# Netzteil_CA1.net
KiCad netlist of a schematic drawn in EAGLE
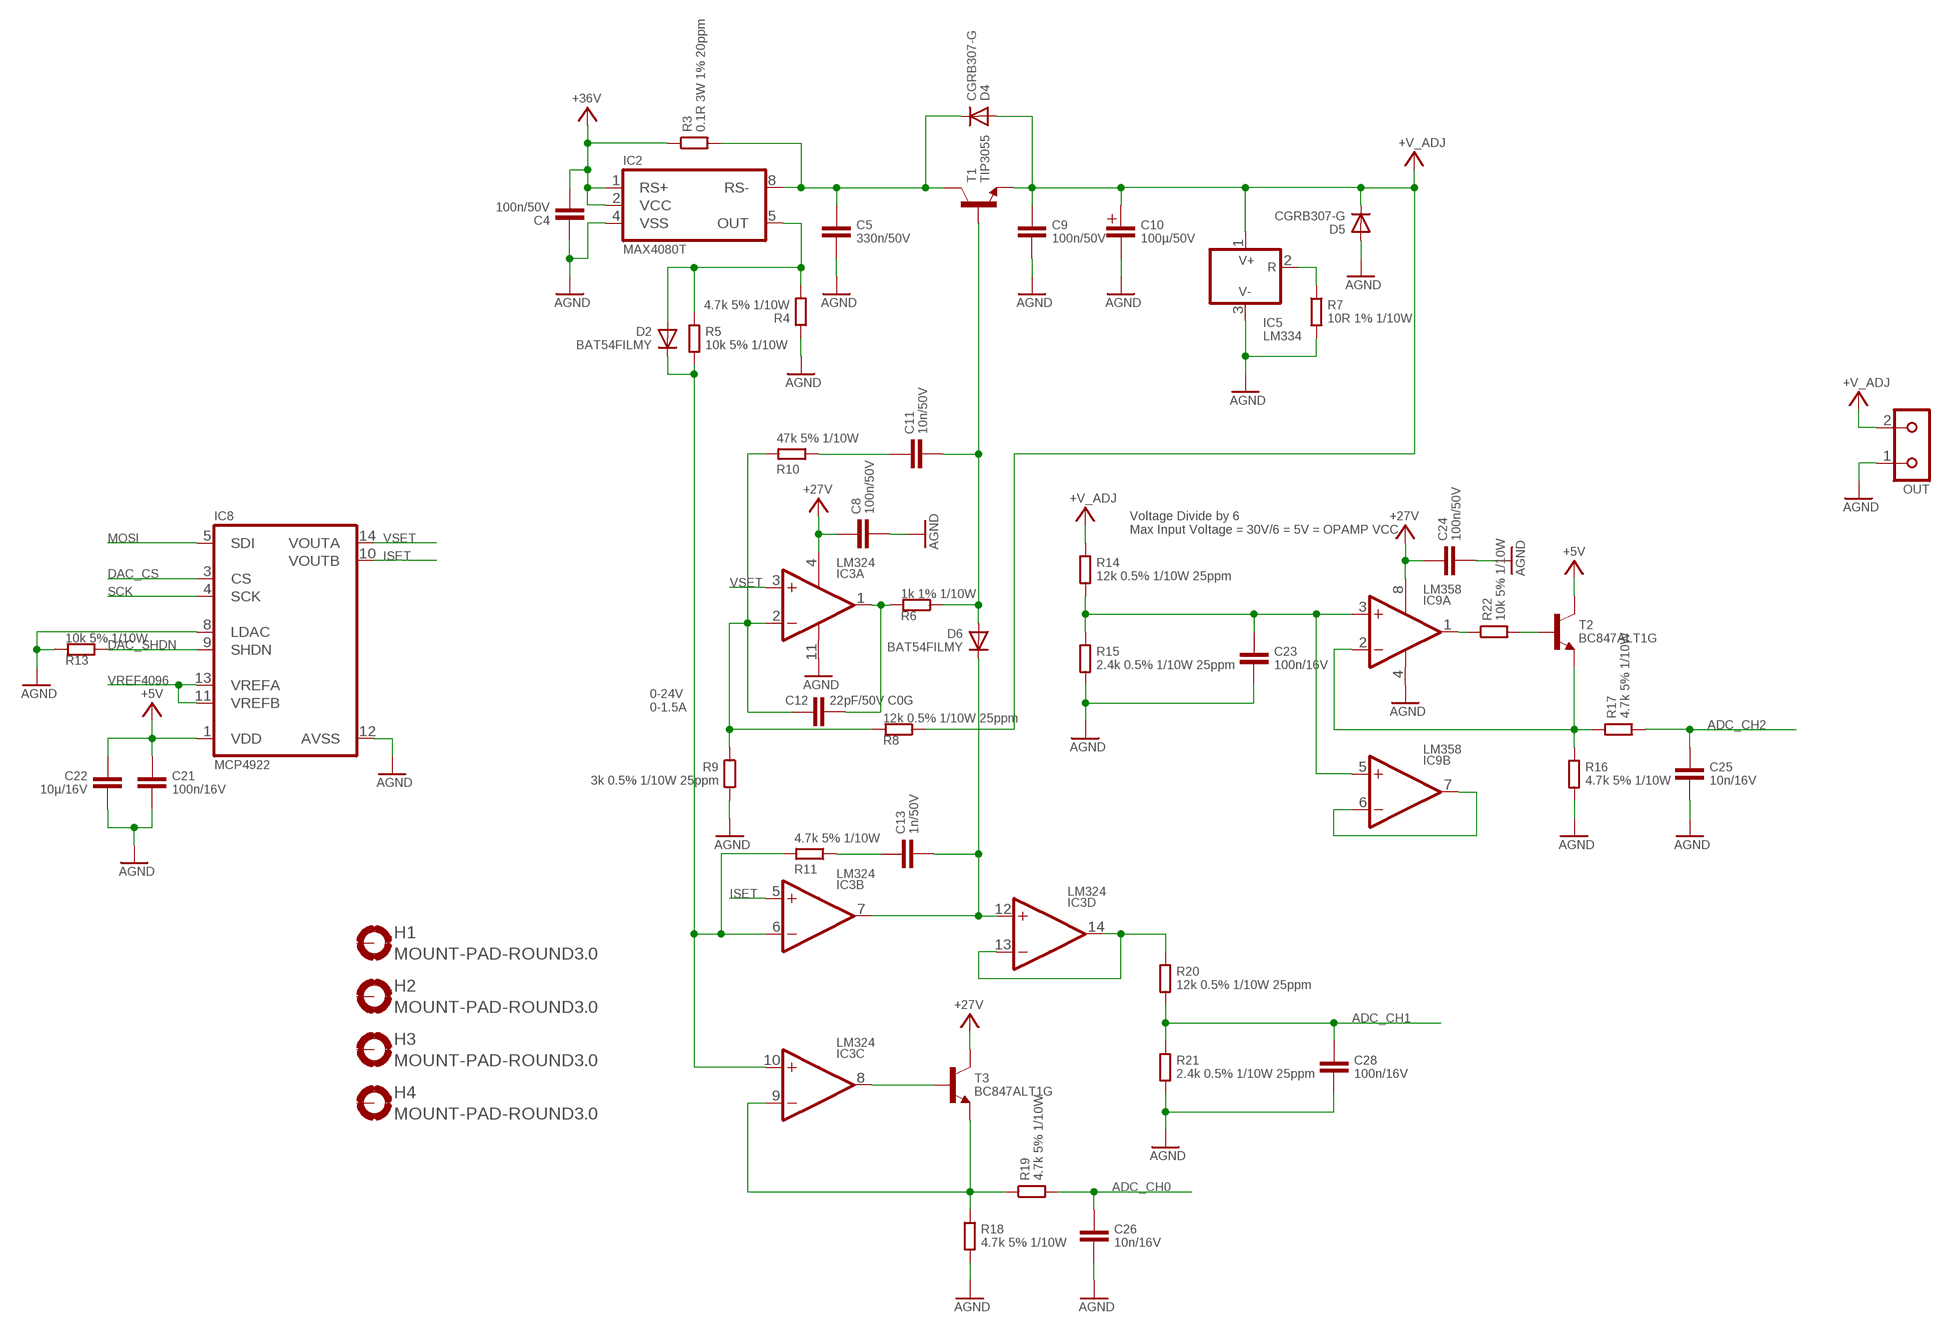
[diagram p0: schematic, sheet 1]
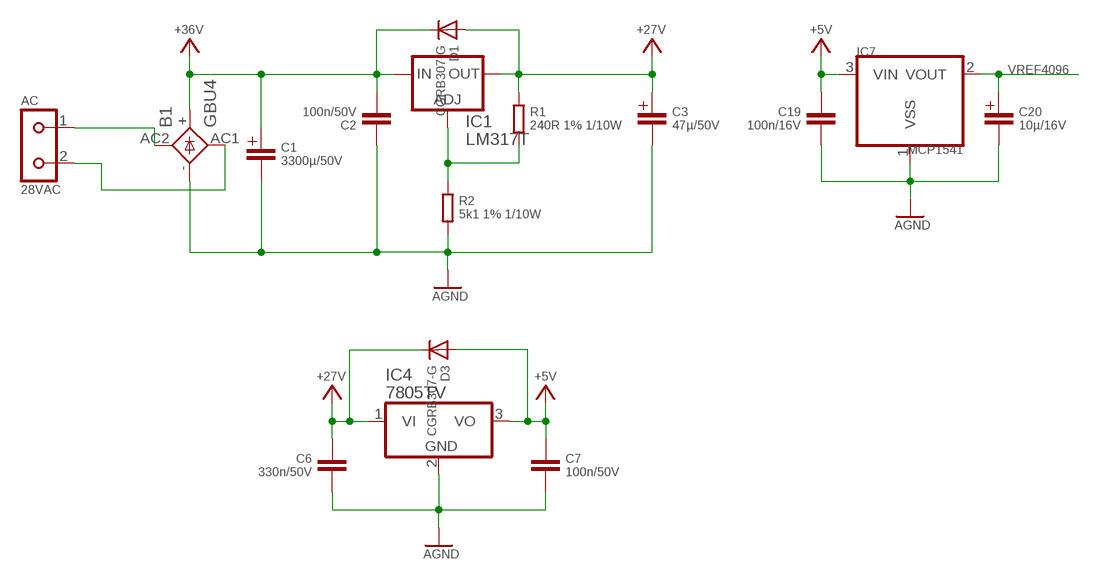
[diagram p1: schematic, sheet 2]
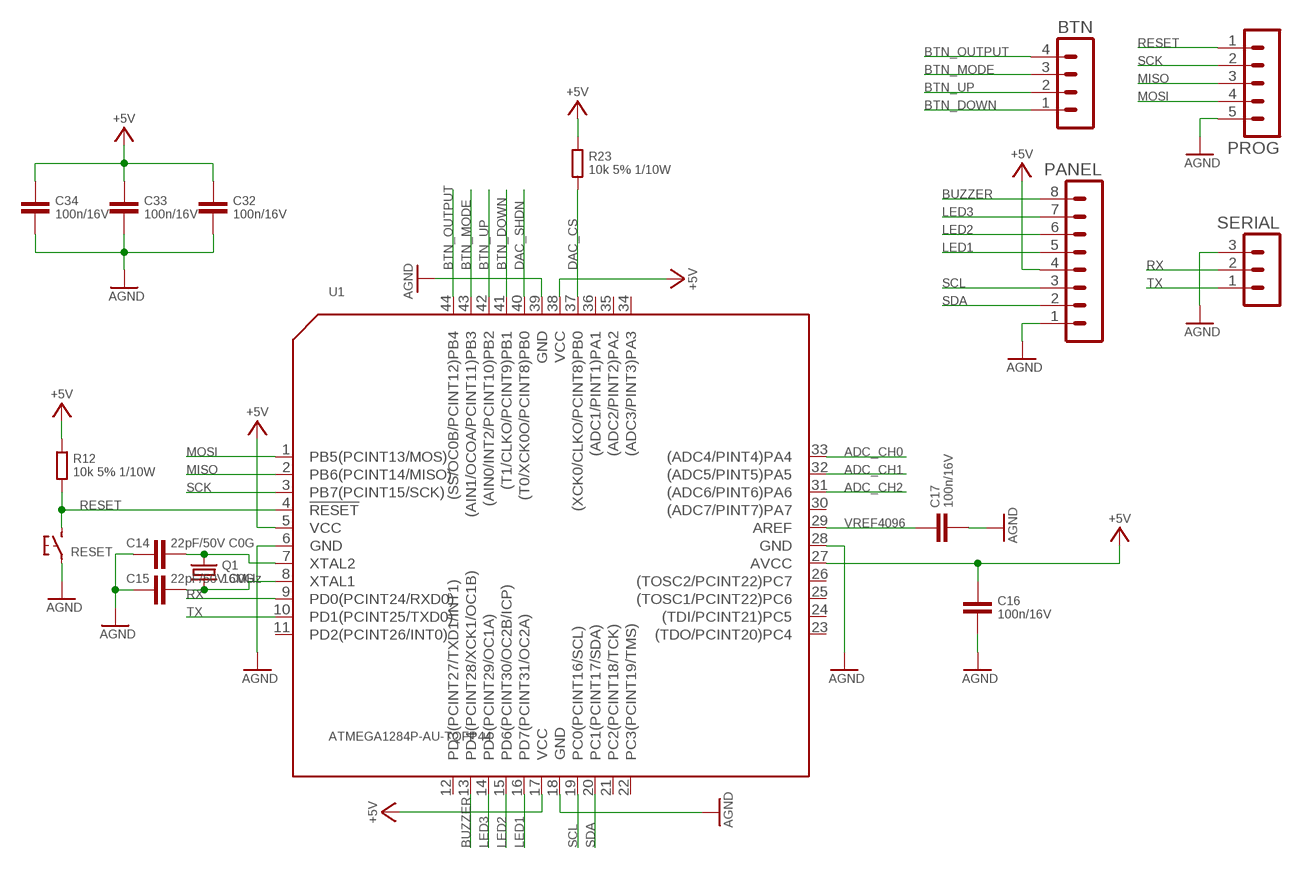
[diagram p2: schematic, sheet 3]

(export (version "E")
  (design (tool "Eeschema 10.0.6"))
  (components
    (comp (ref "AC")
      (value "28VAC")
      (footprint "eagle-import:KL2-691311500002")
      (libsource (lib "eagle-import") (part "KL2691311500002"))
    )
    (comp (ref "B1")
      (value "GBU4")
      (footprint "eagle-import:GBU4S")
      (libsource (lib "eagle-import") (part "GBU8M"))
    )
    (comp (ref "C1")
      (value "3300µ/50V")
      (footprint "eagle-import:C+_7.5_18")
      (libsource (lib "eagle-import") (part "C+7.5/18"))
    )
    (comp (ref "C2")
      (value "100n/50V")
      (footprint "eagle-import:0805")
      (libsource (lib "eagle-import") (part "CC/0805"))
    )
    (comp (ref "C3")
      (value "47µ/50V")
      (footprint "eagle-import:C+_2.5_6.3")
      (libsource (lib "eagle-import") (part "C+2.5/6.3"))
    )
    (comp (ref "C6")
      (value "330n/50V")
      (footprint "eagle-import:0805")
      (libsource (lib "eagle-import") (part "CC/0805"))
    )
    (comp (ref "C7")
      (value "100n/50V")
      (footprint "eagle-import:0805")
      (libsource (lib "eagle-import") (part "CC/0805"))
    )
    (comp (ref "C19")
      (value "100n/16V")
      (footprint "eagle-import:0805")
      (libsource (lib "eagle-import") (part "CC/0805"))
    )
    (comp (ref "C20")
      (value "10µ/16V")
      (footprint "eagle-import:C+_1.5_4")
      (libsource (lib "eagle-import") (part "C+1.5/4"))
    )
    (comp (ref "D1")
      (value "CGRB307-G")
      (footprint "eagle-import:DO214AA-CGRB307-G")
      (libsource (lib "eagle-import") (part "DWIDE"))
    )
    (comp (ref "D3")
      (value "CGRB307-G")
      (footprint "eagle-import:DO214AA-CGRB307-G")
      (libsource (lib "eagle-import") (part "DWIDE"))
    )
    (comp (ref "IC1")
      (value "LM317T")
      (footprint "eagle-import:317TS")
      (libsource (lib "eagle-import") (part "LM317TS"))
    )
    (comp (ref "IC4")
      (value "7805TV")
      (footprint "eagle-import:TO220V")
      (libsource (lib "eagle-import") (part "78TV05"))
    )
    (comp (ref "IC7")
      (value "MCP1541")
      (footprint "eagle-import:TO92-G")
      (libsource (lib "eagle-import") (part "MCP1541"))
    )
    (comp (ref "R1")
      (value "240R 1% 1/10W")
      (footprint "eagle-import:C0805K")
      (libsource (lib "eagle-import") (part "R-SMD0805"))
    )
    (comp (ref "R2")
      (value "5k1 1% 1/10W")
      (footprint "eagle-import:C0805K")
      (libsource (lib "eagle-import") (part "R-SMD0805"))
    )
    (comp (ref "BTN")
      (value "JST-PH-2.0-4P")
      (footprint "eagle-import:JST-PH-2.0-4P")
      (libsource (lib "eagle-import") (part "JST-PH-2.0-4P"))
    )
    (comp (ref "C14")
      (value "22pF/50V C0G")
      (footprint "eagle-import:0805")
      (libsource (lib "eagle-import") (part "CC/0805"))
    )
    (comp (ref "C15")
      (value "22pF/50V C0G")
      (footprint "eagle-import:0805")
      (libsource (lib "eagle-import") (part "CC/0805"))
    )
    (comp (ref "C16")
      (value "100n/16V")
      (footprint "eagle-import:0805")
      (libsource (lib "eagle-import") (part "CC/0805"))
    )
    (comp (ref "C17")
      (value "100n/16V")
      (footprint "eagle-import:0805")
      (libsource (lib "eagle-import") (part "CC/0805"))
    )
    (comp (ref "C32")
      (value "100n/16V")
      (footprint "eagle-import:0805")
      (libsource (lib "eagle-import") (part "CC/0805"))
    )
    (comp (ref "C33")
      (value "100n/16V")
      (footprint "eagle-import:0805")
      (libsource (lib "eagle-import") (part "CC/0805"))
    )
    (comp (ref "C34")
      (value "100n/16V")
      (footprint "eagle-import:0805")
      (libsource (lib "eagle-import") (part "CC/0805"))
    )
    (comp (ref "PANEL")
      (value "JST-PH-2.0-8P")
      (footprint "eagle-import:JST-PH-2.0-8P")
      (libsource (lib "eagle-import") (part "JST-PH-2.0-8P"))
    )
    (comp (ref "PROG")
      (value "MA05-1")
      (footprint "eagle-import:MA05-1")
      (libsource (lib "eagle-import") (part "MA05-1"))
    )
    (comp (ref "Q1")
      (value "16MHz")
      (footprint "eagle-import:Q-5X3.2MM-TXC-7A.SERIES")
      (libsource (lib "eagle-import") (part "Q5X3.2MM-TXC-7A-SERIES"))
    )
    (comp (ref "R12")
      (value "10k 5% 1/10W")
      (footprint "eagle-import:C0805K")
      (libsource (lib "eagle-import") (part "R-SMD0805"))
    )
    (comp (ref "R23")
      (value "10k 5% 1/10W")
      (footprint "eagle-import:C0805K")
      (libsource (lib "eagle-import") (part "R-SMD0805"))
    )
    (comp (ref "RESET")
      (value "TS1B3F-10XX")
      (footprint "eagle-import:B3F-10XX")
      (libsource (lib "eagle-import") (part "TS1B3F-10XX"))
    )
    (comp (ref "SERIAL")
      (value "JST-PH-2.0-3P")
      (footprint "eagle-import:JST-PH-2.0-3P")
      (libsource (lib "eagle-import") (part "JST-PH-2.0-3P"))
    )
    (comp (ref "U1")
      (value "ATMEGA1284P-AU-TQFP44")
      (footprint "eagle-import:TQFP44-0.8-9.6X9.6MM")
      (fields (field (name "MPN") "ATMEGA1284P-AU"))
      (libsource (lib "eagle-import") (part "MCU-ATMEGA1284P-AU(TQFP44)"))
    )
    (comp (ref "C4")
      (value "100n/50V")
      (footprint "eagle-import:0805")
      (libsource (lib "eagle-import") (part "CC/0805"))
    )
    (comp (ref "C5")
      (value "330n/50V")
      (footprint "eagle-import:0805")
      (libsource (lib "eagle-import") (part "CC/0805"))
    )
    (comp (ref "C8")
      (value "100n/50V")
      (footprint "eagle-import:0805")
      (libsource (lib "eagle-import") (part "CC/0805"))
    )
    (comp (ref "C9")
      (value "100n/50V")
      (footprint "eagle-import:0805")
      (libsource (lib "eagle-import") (part "CC/0805"))
    )
    (comp (ref "C10")
      (value "100µ/50V")
      (footprint "eagle-import:C+_3.5_8")
      (libsource (lib "eagle-import") (part "C+3.5/8"))
    )
    (comp (ref "C11")
      (value "10n/50V")
      (footprint "eagle-import:0805")
      (libsource (lib "eagle-import") (part "CC/0805"))
    )
    (comp (ref "C12")
      (value "22pF/50V C0G")
      (footprint "eagle-import:0805")
      (libsource (lib "eagle-import") (part "CC/0805"))
    )
    (comp (ref "C13")
      (value "1n/50V")
      (footprint "eagle-import:0805")
      (libsource (lib "eagle-import") (part "CC/0805"))
    )
    (comp (ref "C21")
      (value "100n/16V")
      (footprint "eagle-import:0805")
      (libsource (lib "eagle-import") (part "CC/0805"))
    )
    (comp (ref "C22")
      (value "10µ/16V")
      (footprint "eagle-import:1206")
      (libsource (lib "eagle-import") (part "CC/1206"))
    )
    (comp (ref "C23")
      (value "100n/16V")
      (footprint "eagle-import:0805")
      (libsource (lib "eagle-import") (part "CC/0805"))
    )
    (comp (ref "C24")
      (value "100n/50V")
      (footprint "eagle-import:0805")
      (libsource (lib "eagle-import") (part "CC/0805"))
    )
    (comp (ref "C25")
      (value "10n/16V")
      (footprint "eagle-import:0805")
      (libsource (lib "eagle-import") (part "CC/0805"))
    )
    (comp (ref "C26")
      (value "10n/16V")
      (footprint "eagle-import:0805")
      (libsource (lib "eagle-import") (part "CC/0805"))
    )
    (comp (ref "C28")
      (value "100n/16V")
      (footprint "eagle-import:0805")
      (libsource (lib "eagle-import") (part "CC/0805"))
    )
    (comp (ref "D2")
      (value "BAT54FILMY")
      (footprint "eagle-import:SOT23")
      (libsource (lib "eagle-import") (part "DBAT54FILMY"))
    )
    (comp (ref "D4")
      (value "CGRB307-G")
      (footprint "eagle-import:DO214AA-CGRB307-G")
      (libsource (lib "eagle-import") (part "DWIDE"))
    )
    (comp (ref "D5")
      (value "CGRB307-G")
      (footprint "eagle-import:DO214AA-CGRB307-G")
      (libsource (lib "eagle-import") (part "DWIDE"))
    )
    (comp (ref "D6")
      (value "BAT54FILMY")
      (footprint "eagle-import:SOT23")
      (libsource (lib "eagle-import") (part "DBAT54FILMY"))
    )
    (comp (ref "H1")
      (value "MOUNT-PAD-ROUND3.0")
      (footprint "eagle-import:3,0-PAD")
      (libsource (lib "eagle-import") (part "MOUNT-PAD-ROUND3.0"))
    )
    (comp (ref "H2")
      (value "MOUNT-PAD-ROUND3.0")
      (footprint "eagle-import:3,0-PAD")
      (libsource (lib "eagle-import") (part "MOUNT-PAD-ROUND3.0"))
    )
    (comp (ref "H3")
      (value "MOUNT-PAD-ROUND3.0")
      (footprint "eagle-import:3,0-PAD")
      (libsource (lib "eagle-import") (part "MOUNT-PAD-ROUND3.0"))
    )
    (comp (ref "H4")
      (value "MOUNT-PAD-ROUND3.0")
      (footprint "eagle-import:3,0-PAD")
      (libsource (lib "eagle-import") (part "MOUNT-PAD-ROUND3.0"))
    )
    (comp (ref "IC2")
      (value "MAX4080T")
      (footprint "eagle-import:SOP8")
      (libsource (lib "eagle-import") (part "MAX4080"))
    )
    (comp (ref "IC3")
      (value "LM324")
      (footprint "eagle-import:SO14")
      (fields (field (name "OC_MOUSER") "595-LM324ADR"))
      (libsource (lib "eagle-import") (part "QUAD-OPVOPA4197"))
    )
    (comp (ref "IC5")
      (value "LM334")
      (footprint "eagle-import:TO92-G")
      (libsource (lib "eagle-import") (part "LM334"))
    )
    (comp (ref "IC8")
      (value "MCP4922")
      (footprint "eagle-import:TSSOP14")
      (libsource (lib "eagle-import") (part "MCP4922"))
    )
    (comp (ref "IC9")
      (value "LM358")
      (footprint "eagle-import:SOP8")
      (fields (field (name "OC_MOUSER") "595-LM358ADR"))
      (libsource (lib "eagle-import") (part "DUAL-OPVSOP8"))
    )
    (comp (ref "OUT")
      (value "KL2691311500002")
      (footprint "eagle-import:KL2-691311500002")
      (libsource (lib "eagle-import") (part "KL2691311500002"))
    )
    (comp (ref "R3")
      (value "0.1R 3W 1% 20ppm")
      (footprint "eagle-import:GMR100")
      (libsource (lib "eagle-import") (part "R-SMDGMR100"))
    )
    (comp (ref "R4")
      (value "4.7k 5% 1/10W")
      (footprint "eagle-import:C0805K")
      (libsource (lib "eagle-import") (part "R-SMD0805"))
    )
    (comp (ref "R5")
      (value "10k 5% 1/10W")
      (footprint "eagle-import:C0805K")
      (libsource (lib "eagle-import") (part "R-SMD0805"))
    )
    (comp (ref "R6")
      (value "1k 1% 1/10W")
      (footprint "eagle-import:C0805K")
      (libsource (lib "eagle-import") (part "R-SMD0805"))
    )
    (comp (ref "R7")
      (value "10R 1% 1/10W")
      (footprint "eagle-import:C0805K")
      (libsource (lib "eagle-import") (part "R-SMD0805"))
    )
    (comp (ref "R8")
      (value "12k 0.5% 1/10W 25ppm")
      (footprint "eagle-import:C0805K")
      (libsource (lib "eagle-import") (part "R-SMD0805"))
    )
    (comp (ref "R9")
      (value "3k 0.5% 1/10W 25ppm")
      (footprint "eagle-import:C0805K")
      (libsource (lib "eagle-import") (part "R-SMD0805"))
    )
    (comp (ref "R10")
      (value "47k 5% 1/10W")
      (footprint "eagle-import:C0805K")
      (libsource (lib "eagle-import") (part "R-SMD0805"))
    )
    (comp (ref "R11")
      (value "4.7k 5% 1/10W")
      (footprint "eagle-import:C0805K")
      (libsource (lib "eagle-import") (part "R-SMD0805"))
    )
    (comp (ref "R13")
      (value "10k 5% 1/10W")
      (footprint "eagle-import:C0805K")
      (libsource (lib "eagle-import") (part "R-SMD0805"))
    )
    (comp (ref "R14")
      (value "12k 0.5% 1/10W 25ppm")
      (footprint "eagle-import:C0805K")
      (libsource (lib "eagle-import") (part "R-SMD0805"))
    )
    (comp (ref "R15")
      (value "2.4k 0.5% 1/10W 25ppm")
      (footprint "eagle-import:C0805K")
      (libsource (lib "eagle-import") (part "R-SMD0805"))
    )
    (comp (ref "R16")
      (value "4.7k 5% 1/10W")
      (footprint "eagle-import:C0805K")
      (libsource (lib "eagle-import") (part "R-SMD0805"))
    )
    (comp (ref "R17")
      (value "4.7k 5% 1/10W")
      (footprint "eagle-import:C0805K")
      (libsource (lib "eagle-import") (part "R-SMD0805"))
    )
    (comp (ref "R18")
      (value "4.7k 5% 1/10W")
      (footprint "eagle-import:C0805K")
      (libsource (lib "eagle-import") (part "R-SMD0805"))
    )
    (comp (ref "R19")
      (value "4.7k 5% 1/10W")
      (footprint "eagle-import:C0805K")
      (libsource (lib "eagle-import") (part "R-SMD0805"))
    )
    (comp (ref "R20")
      (value "12k 0.5% 1/10W 25ppm")
      (footprint "eagle-import:C0805K")
      (libsource (lib "eagle-import") (part "R-SMD0805"))
    )
    (comp (ref "R21")
      (value "2.4k 0.5% 1/10W 25ppm")
      (footprint "eagle-import:C0805K")
      (libsource (lib "eagle-import") (part "R-SMD0805"))
    )
    (comp (ref "R22")
      (value "10k 5% 1/10W")
      (footprint "eagle-import:C0805K")
      (libsource (lib "eagle-import") (part "R-SMD0805"))
    )
    (comp (ref "T1")
      (value "TIP3055")
      (footprint "eagle-import:TOP3AV")
      (libsource (lib "eagle-import") (part "T-NPNTOP3AV-BCE"))
    )
    (comp (ref "T2")
      (value "BC847ALT1G")
      (footprint "eagle-import:SOT23-BEC")
      (libsource (lib "eagle-import") (part "T-NPNSOT23-BEC"))
    )
    (comp (ref "T3")
      (value "BC847ALT1G")
      (footprint "eagle-import:SOT23-BEC")
      (libsource (lib "eagle-import") (part "T-NPNSOT23-BEC"))
    )
  )
  (nets
    (net (code "1") (name "+5V") (class "Default")
      (node (ref "C16") (pin "1") (pinfunction "1_1") (pintype "passive"))
      (node (ref "C19") (pin "1") (pinfunction "1_1") (pintype "passive"))
      (node (ref "C21") (pin "1") (pinfunction "1_1") (pintype "passive"))
      (node (ref "C22") (pin "1") (pinfunction "1_1") (pintype "passive"))
      (node (ref "C32") (pin "1") (pinfunction "1_1") (pintype "passive"))
      (node (ref "C33") (pin "1") (pinfunction "1_1") (pintype "passive"))
      (node (ref "C34") (pin "1") (pinfunction "1_1") (pintype "passive"))
      (node (ref "C7") (pin "1") (pinfunction "1_1") (pintype "passive"))
      (node (ref "D3") (pin "A") (pinfunction "A_A") (pintype "passive"))
      (node (ref "IC4") (pin "3") (pinfunction "VO_3") (pintype "passive"))
      (node (ref "IC7") (pin "3") (pinfunction "VIN_3") (pintype "power_in"))
      (node (ref "IC8") (pin "1") (pinfunction "VDD_1") (pintype "power_in"))
      (node (ref "PANEL") (pin "4") (pinfunction "4_4") (pintype "passive"))
      (node (ref "R12") (pin "1") (pinfunction "1_1") (pintype "passive"))
      (node (ref "R23") (pin "1") (pinfunction "1_1") (pintype "passive"))
      (node (ref "T2") (pin "C") (pinfunction "C_C") (pintype "passive"))
      (node (ref "U1") (pin "17") (pinfunction "VCC_17") (pintype "bidirectional"))
      (node (ref "U1") (pin "27") (pinfunction "AVCC_27") (pintype "bidirectional"))
      (node (ref "U1") (pin "38") (pinfunction "VCC_38") (pintype "bidirectional"))
      (node (ref "U1") (pin "5") (pinfunction "VCC_5") (pintype "bidirectional"))
    )
    (net (code "2") (name "+27V") (class "Default")
      (node (ref "C24") (pin "1") (pinfunction "1_1") (pintype "passive"))
      (node (ref "C3") (pin "+") (pinfunction "+_+") (pintype "passive"))
      (node (ref "C6") (pin "1") (pinfunction "1_1") (pintype "passive"))
      (node (ref "C8") (pin "1") (pinfunction "1_1") (pintype "passive"))
      (node (ref "D1") (pin "A") (pinfunction "A_A") (pintype "passive"))
      (node (ref "D3") (pin "C") (pinfunction "C_C") (pintype "passive"))
      (node (ref "IC1") (pin "2") (pinfunction "OUT_2") (pintype "passive"))
      (node (ref "IC3") (pin "4") (pinfunction "V+_4") (pintype "power_in"))
      (node (ref "IC4") (pin "1") (pinfunction "VI_1") (pintype "input"))
      (node (ref "IC9") (pin "8") (pinfunction "V+_8") (pintype "power_in"))
      (node (ref "R1") (pin "1") (pinfunction "1_1") (pintype "passive"))
      (node (ref "T3") (pin "C") (pinfunction "C_C") (pintype "passive"))
    )
    (net (code "3") (name "+36V") (class "Default")
      (node (ref "B1") (pin "+") (pinfunction "+_+") (pintype "passive"))
      (node (ref "C1") (pin "+") (pinfunction "+_+") (pintype "passive"))
      (node (ref "C2") (pin "2") (pinfunction "2_2") (pintype "passive"))
      (node (ref "C4") (pin "2") (pinfunction "2_2") (pintype "passive"))
      (node (ref "D1") (pin "C") (pinfunction "C_C") (pintype "passive"))
      (node (ref "IC1") (pin "3") (pinfunction "IN_3") (pintype "input"))
      (node (ref "IC2") (pin "1") (pinfunction "RS+_1") (pintype "input"))
      (node (ref "IC2") (pin "2") (pinfunction "VCC_2") (pintype "power_in"))
      (node (ref "R3") (pin "1") (pinfunction "1_1") (pintype "passive"))
    )
    (net (code "4") (name "+V_ADJ") (class "Default")
      (node (ref "C10") (pin "+") (pinfunction "+_+") (pintype "passive"))
      (node (ref "C9") (pin "1") (pinfunction "1_1") (pintype "passive"))
      (node (ref "D4") (pin "A") (pinfunction "A_A") (pintype "passive"))
      (node (ref "D5") (pin "C") (pinfunction "C_C") (pintype "passive"))
      (node (ref "IC5") (pin "1") (pinfunction "V+_1") (pintype "passive"))
      (node (ref "OUT") (pin "2") (pinfunction "2_2") (pintype "passive"))
      (node (ref "R14") (pin "1") (pinfunction "1_1") (pintype "passive"))
      (node (ref "R8") (pin "1") (pinfunction "1_1") (pintype "passive"))
      (node (ref "T1") (pin "E") (pinfunction "E_E") (pintype "passive"))
    )
    (net (code "5") (name "ADC_CH0") (class "Default")
      (node (ref "C26") (pin "1") (pinfunction "1_1") (pintype "passive"))
      (node (ref "R19") (pin "2") (pinfunction "2_2") (pintype "passive"))
      (node (ref "U1") (pin "33") (pinfunction "(ADC4/PINT4)PA4_33") (pintype "bidirectional"))
    )
    (net (code "6") (name "ADC_CH1") (class "Default")
      (node (ref "C28") (pin "1") (pinfunction "1_1") (pintype "passive"))
      (node (ref "R20") (pin "2") (pinfunction "2_2") (pintype "passive"))
      (node (ref "R21") (pin "1") (pinfunction "1_1") (pintype "passive"))
      (node (ref "U1") (pin "32") (pinfunction "(ADC5/PINT5)PA5_32") (pintype "bidirectional"))
    )
    (net (code "7") (name "ADC_CH2") (class "Default")
      (node (ref "C25") (pin "1") (pinfunction "1_1") (pintype "passive"))
      (node (ref "R17") (pin "2") (pinfunction "2_2") (pintype "passive"))
      (node (ref "U1") (pin "31") (pinfunction "(ADC6/PINT6)PA6_31") (pintype "bidirectional"))
    )
    (net (code "8") (name "AGND") (class "Default")
      (node (ref "B1") (pin "-") (pinfunction "-_-") (pintype "passive"))
      (node (ref "C1") (pin "-") (pinfunction "-_-") (pintype "passive"))
      (node (ref "C10") (pin "-") (pinfunction "-_-") (pintype "passive"))
      (node (ref "C14") (pin "1") (pinfunction "1_1") (pintype "passive"))
      (node (ref "C15") (pin "1") (pinfunction "1_1") (pintype "passive"))
      (node (ref "C16") (pin "2") (pinfunction "2_2") (pintype "passive"))
      (node (ref "C17") (pin "2") (pinfunction "2_2") (pintype "passive"))
      (node (ref "C19") (pin "2") (pinfunction "2_2") (pintype "passive"))
      (node (ref "C2") (pin "1") (pinfunction "1_1") (pintype "passive"))
      (node (ref "C20") (pin "-") (pinfunction "-_-") (pintype "passive"))
      (node (ref "C21") (pin "2") (pinfunction "2_2") (pintype "passive"))
      (node (ref "C22") (pin "2") (pinfunction "2_2") (pintype "passive"))
      (node (ref "C23") (pin "2") (pinfunction "2_2") (pintype "passive"))
      (node (ref "C24") (pin "2") (pinfunction "2_2") (pintype "passive"))
      (node (ref "C25") (pin "2") (pinfunction "2_2") (pintype "passive"))
      (node (ref "C26") (pin "2") (pinfunction "2_2") (pintype "passive"))
      (node (ref "C28") (pin "2") (pinfunction "2_2") (pintype "passive"))
      (node (ref "C3") (pin "-") (pinfunction "-_-") (pintype "passive"))
      (node (ref "C32") (pin "2") (pinfunction "2_2") (pintype "passive"))
      (node (ref "C33") (pin "2") (pinfunction "2_2") (pintype "passive"))
      (node (ref "C34") (pin "2") (pinfunction "2_2") (pintype "passive"))
      (node (ref "C4") (pin "1") (pinfunction "1_1") (pintype "passive"))
      (node (ref "C5") (pin "2") (pinfunction "2_2") (pintype "passive"))
      (node (ref "C6") (pin "2") (pinfunction "2_2") (pintype "passive"))
      (node (ref "C7") (pin "2") (pinfunction "2_2") (pintype "passive"))
      (node (ref "C8") (pin "2") (pinfunction "2_2") (pintype "passive"))
      (node (ref "C9") (pin "2") (pinfunction "2_2") (pintype "passive"))
      (node (ref "D5") (pin "A") (pinfunction "A_A") (pintype "passive"))
      (node (ref "IC2") (pin "4") (pinfunction "VSS_4") (pintype "power_in"))
      (node (ref "IC3") (pin "11") (pinfunction "V-_11") (pintype "power_in"))
      (node (ref "IC4") (pin "2") (pinfunction "GND_2") (pintype "passive"))
      (node (ref "IC5") (pin "3") (pinfunction "V-_3") (pintype "passive"))
      (node (ref "IC7") (pin "1") (pinfunction "VSS_1") (pintype "power_in"))
      (node (ref "IC8") (pin "12") (pinfunction "AVSS_12") (pintype "power_in"))
      (node (ref "IC8") (pin "8") (pinfunction "LDAC_8") (pintype "input"))
      (node (ref "IC9") (pin "4") (pinfunction "V-_4") (pintype "power_in"))
      (node (ref "OUT") (pin "1") (pinfunction "1_1") (pintype "passive"))
      (node (ref "PANEL") (pin "1") (pinfunction "1_1") (pintype "passive"))
      (node (ref "PROG") (pin "5") (pinfunction "5_5") (pintype "passive"))
      (node (ref "R13") (pin "2") (pinfunction "2_2") (pintype "passive"))
      (node (ref "R15") (pin "2") (pinfunction "2_2") (pintype "passive"))
      (node (ref "R16") (pin "2") (pinfunction "2_2") (pintype "passive"))
      (node (ref "R18") (pin "2") (pinfunction "2_2") (pintype "passive"))
      (node (ref "R2") (pin "2") (pinfunction "2_2") (pintype "passive"))
      (node (ref "R21") (pin "2") (pinfunction "2_2") (pintype "passive"))
      (node (ref "R4") (pin "1") (pinfunction "1_1") (pintype "passive"))
      (node (ref "R7") (pin "2") (pinfunction "2_2") (pintype "passive"))
      (node (ref "R9") (pin "2") (pinfunction "2_2") (pintype "passive"))
      (node (ref "RESET") (pin "1") (pinfunction "1_1") (pintype "passive"))
      (node (ref "SERIAL") (pin "3") (pinfunction "3_3") (pintype "passive"))
      (node (ref "U1") (pin "18") (pinfunction "GND_18") (pintype "bidirectional"))
      (node (ref "U1") (pin "28") (pinfunction "GND_28") (pintype "bidirectional"))
      (node (ref "U1") (pin "39") (pinfunction "GND_39") (pintype "bidirectional"))
      (node (ref "U1") (pin "6") (pinfunction "GND_6") (pintype "bidirectional"))
    )
    (net (code "9") (name "BTN_DOWN") (class "Default")
      (node (ref "BTN") (pin "1") (pinfunction "1_1") (pintype "passive"))
      (node (ref "U1") (pin "41") (pinfunction "(T1/CLKO/PCINT9)PB1_41") (pintype "bidirectional"))
    )
    (net (code "10") (name "BTN_MODE") (class "Default")
      (node (ref "BTN") (pin "3") (pinfunction "3_3") (pintype "passive"))
      (node (ref "U1") (pin "43") (pinfunction "(AIN1/OCOA/PCINT11)PB3_43") (pintype "bidirectional"))
    )
    (net (code "11") (name "BTN_OUTPUT") (class "Default")
      (node (ref "BTN") (pin "4") (pinfunction "4_4") (pintype "passive"))
      (node (ref "U1") (pin "44") (pinfunction "(SS/OC0B/PCINT12)PB4_44") (pintype "bidirectional"))
    )
    (net (code "12") (name "BTN_UP") (class "Default")
      (node (ref "BTN") (pin "2") (pinfunction "2_2") (pintype "passive"))
      (node (ref "U1") (pin "42") (pinfunction "(AIN0/INT2/PCINT10)PB2_42") (pintype "bidirectional"))
    )
    (net (code "13") (name "BUZZER") (class "Default")
      (node (ref "PANEL") (pin "8") (pinfunction "8_8") (pintype "passive"))
      (node (ref "U1") (pin "13") (pinfunction "PD4(PCINT28/XCK1/OC1B)_13") (pintype "bidirectional"))
    )
    (net (code "14") (name "DAC_CS") (class "Default")
      (node (ref "IC8") (pin "3") (pinfunction "CS_3") (pintype "input"))
      (node (ref "R23") (pin "2") (pinfunction "2_2") (pintype "passive"))
      (node (ref "U1") (pin "37") (pinfunction "(XCK0/CLKO/PCINT8)PB0_37") (pintype "bidirectional"))
    )
    (net (code "15") (name "DAC_SHDN") (class "Default")
      (node (ref "IC8") (pin "9") (pinfunction "SHDN_9") (pintype "input"))
      (node (ref "R13") (pin "1") (pinfunction "1_1") (pintype "passive"))
      (node (ref "U1") (pin "40") (pinfunction "(T0/XCK0O/PCINT8)PB0_40") (pintype "bidirectional"))
    )
    (net (code "16") (name "ISET") (class "Default")
      (node (ref "IC3") (pin "5") (pinfunction "+IN_5") (pintype "input"))
      (node (ref "IC8") (pin "10") (pinfunction "VOUTB_10") (pintype "output"))
    )
    (net (code "17") (name "LED1") (class "Default")
      (node (ref "PANEL") (pin "5") (pinfunction "5_5") (pintype "passive"))
      (node (ref "U1") (pin "16") (pinfunction "PD7(PCINT31/OC2A)_16") (pintype "bidirectional"))
    )
    (net (code "18") (name "LED2") (class "Default")
      (node (ref "PANEL") (pin "6") (pinfunction "6_6") (pintype "passive"))
      (node (ref "U1") (pin "15") (pinfunction "PD6(PCINT30/OC2B/ICP)_15") (pintype "bidirectional"))
    )
    (net (code "19") (name "LED3") (class "Default")
      (node (ref "PANEL") (pin "7") (pinfunction "7_7") (pintype "passive"))
      (node (ref "U1") (pin "14") (pinfunction "PD5(PCINT29/OC1A)_14") (pintype "bidirectional"))
    )
    (net (code "20") (name "MISO") (class "Default")
      (node (ref "PROG") (pin "3") (pinfunction "3_3") (pintype "passive"))
      (node (ref "U1") (pin "2") (pinfunction "PB6(PCINT14/MISO)_2") (pintype "bidirectional"))
    )
    (net (code "21") (name "MOSI") (class "Default")
      (node (ref "IC8") (pin "5") (pinfunction "SDI_5") (pintype "input"))
      (node (ref "PROG") (pin "4") (pinfunction "4_4") (pintype "passive"))
      (node (ref "U1") (pin "1") (pinfunction "PB5(PCINT13/MOS)_1") (pintype "bidirectional"))
    )
    (net (code "22") (name "Net-(B1-AC1)") (class "Default")
      (node (ref "AC") (pin "1") (pinfunction "1_1") (pintype "passive"))
      (node (ref "B1") (pin "AC2") (pinfunction "AC1_AC2") (pintype "passive"))
    )
    (net (code "23") (name "Net-(B1-AC2)") (class "Default")
      (node (ref "AC") (pin "2") (pinfunction "2_2") (pintype "passive"))
      (node (ref "B1") (pin "AC1") (pinfunction "AC2_AC1") (pintype "passive"))
    )
    (net (code "24") (name "Net-(C11-Pad1)") (class "Default")
      (node (ref "C11") (pin "1") (pinfunction "1_1") (pintype "passive"))
      (node (ref "R10") (pin "1") (pinfunction "1_1") (pintype "passive"))
    )
    (net (code "25") (name "Net-(C13-Pad1)") (class "Default")
      (node (ref "C13") (pin "1") (pinfunction "1_1") (pintype "passive"))
      (node (ref "R11") (pin "1") (pinfunction "1_1") (pintype "passive"))
    )
    (net (code "26") (name "Net-(D2-A)") (class "Default")
      (node (ref "D2") (pin "1") (pinfunction "A_1") (pintype "passive"))
      (node (ref "IC2") (pin "5") (pinfunction "OUT_5") (pintype "bidirectional"))
      (node (ref "R4") (pin "2") (pinfunction "2_2") (pintype "passive"))
      (node (ref "R5") (pin "1") (pinfunction "1_1") (pintype "passive"))
    )
    (net (code "27") (name "Net-(D2-C)") (class "Default")
      (node (ref "D2") (pin "3") (pinfunction "C_3") (pintype "passive"))
      (node (ref "IC3") (pin "10") (pinfunction "+IN_10") (pintype "input"))
      (node (ref "IC3") (pin "6") (pinfunction "-IN_6") (pintype "input"))
      (node (ref "R11") (pin "2") (pinfunction "2_2") (pintype "passive"))
      (node (ref "R5") (pin "2") (pinfunction "2_2") (pintype "passive"))
    )
    (net (code "28") (name "Net-(D6-A)") (class "Default")
      (node (ref "C11") (pin "2") (pinfunction "2_2") (pintype "passive"))
      (node (ref "D6") (pin "1") (pinfunction "A_1") (pintype "passive"))
      (node (ref "R6") (pin "1") (pinfunction "1_1") (pintype "passive"))
      (node (ref "T1") (pin "B") (pinfunction "B_B") (pintype "passive"))
    )
    (net (code "29") (name "Net-(D6-C)") (class "Default")
      (node (ref "C13") (pin "2") (pinfunction "2_2") (pintype "passive"))
      (node (ref "D6") (pin "3") (pinfunction "C_3") (pintype "passive"))
      (node (ref "IC3") (pin "12") (pinfunction "+IN_12") (pintype "input"))
      (node (ref "IC3") (pin "7") (pinfunction "OUT_7") (pintype "output"))
    )
    (net (code "30") (name "Net-(IC1-ADJ)") (class "Default")
      (node (ref "IC1") (pin "1") (pinfunction "ADJ_1") (pintype "input"))
      (node (ref "R1") (pin "2") (pinfunction "2_2") (pintype "passive"))
      (node (ref "R2") (pin "1") (pinfunction "1_1") (pintype "passive"))
    )
    (net (code "31") (name "Net-(IC2-RS-)") (class "Default")
      (node (ref "C5") (pin "1") (pinfunction "1_1") (pintype "passive"))
      (node (ref "D4") (pin "C") (pinfunction "C_C") (pintype "passive"))
      (node (ref "IC2") (pin "8") (pinfunction "RS-_8") (pintype "input"))
      (node (ref "R3") (pin "2") (pinfunction "2_2") (pintype "passive"))
      (node (ref "T1") (pin "C") (pinfunction "C_C") (pintype "passive"))
    )
    (net (code "32") (name "Net-(IC3A--IN)") (class "Default")
      (node (ref "C12") (pin "1") (pinfunction "1_1") (pintype "passive"))
      (node (ref "IC3") (pin "2") (pinfunction "-IN_2") (pintype "input"))
      (node (ref "R10") (pin "2") (pinfunction "2_2") (pintype "passive"))
      (node (ref "R8") (pin "2") (pinfunction "2_2") (pintype "passive"))
      (node (ref "R9") (pin "1") (pinfunction "1_1") (pintype "passive"))
    )
    (net (code "33") (name "Net-(IC3A-OUT)") (class "Default")
      (node (ref "C12") (pin "2") (pinfunction "2_2") (pintype "passive"))
      (node (ref "IC3") (pin "1") (pinfunction "OUT_1") (pintype "output"))
      (node (ref "R6") (pin "2") (pinfunction "2_2") (pintype "passive"))
    )
    (net (code "34") (name "Net-(IC3C--IN)") (class "Default")
      (node (ref "IC3") (pin "9") (pinfunction "-IN_9") (pintype "input"))
      (node (ref "R18") (pin "1") (pinfunction "1_1") (pintype "passive"))
      (node (ref "R19") (pin "1") (pinfunction "1_1") (pintype "passive"))
      (node (ref "T3") (pin "E") (pinfunction "E_E") (pintype "passive"))
    )
    (net (code "35") (name "Net-(IC3C-OUT)") (class "Default")
      (node (ref "IC3") (pin "8") (pinfunction "OUT_8") (pintype "output"))
      (node (ref "T3") (pin "B") (pinfunction "B_B") (pintype "passive"))
    )
    (net (code "36") (name "Net-(IC3D--IN)") (class "Default")
      (node (ref "IC3") (pin "13") (pinfunction "-IN_13") (pintype "input"))
      (node (ref "IC3") (pin "14") (pinfunction "OUT_14") (pintype "output"))
      (node (ref "R20") (pin "1") (pinfunction "1_1") (pintype "passive"))
    )
    (net (code "37") (name "Net-(IC5-R)") (class "Default")
      (node (ref "IC5") (pin "2") (pinfunction "R_2") (pintype "input"))
      (node (ref "R7") (pin "1") (pinfunction "1_1") (pintype "passive"))
    )
    (net (code "38") (name "Net-(IC9A-+IN)") (class "Default")
      (node (ref "C23") (pin "1") (pinfunction "1_1") (pintype "passive"))
      (node (ref "IC9") (pin "3") (pinfunction "+IN_3") (pintype "input"))
      (node (ref "IC9") (pin "5") (pinfunction "+IN_5") (pintype "input"))
      (node (ref "R14") (pin "2") (pinfunction "2_2") (pintype "passive"))
      (node (ref "R15") (pin "1") (pinfunction "1_1") (pintype "passive"))
    )
    (net (code "39") (name "Net-(IC9A--IN)") (class "Default")
      (node (ref "IC9") (pin "2") (pinfunction "-IN_2") (pintype "input"))
      (node (ref "R16") (pin "1") (pinfunction "1_1") (pintype "passive"))
      (node (ref "R17") (pin "1") (pinfunction "1_1") (pintype "passive"))
      (node (ref "T2") (pin "E") (pinfunction "E_E") (pintype "passive"))
    )
    (net (code "40") (name "Net-(IC9A-OUT)") (class "Default")
      (node (ref "IC9") (pin "1") (pinfunction "OUT_1") (pintype "output"))
      (node (ref "R22") (pin "1") (pinfunction "1_1") (pintype "passive"))
    )
    (net (code "41") (name "Net-(IC9B--IN)") (class "Default")
      (node (ref "IC9") (pin "6") (pinfunction "-IN_6") (pintype "input"))
      (node (ref "IC9") (pin "7") (pinfunction "OUT_7") (pintype "output"))
    )
    (net (code "42") (name "Net-(R22-Pad2)") (class "Default")
      (node (ref "R22") (pin "2") (pinfunction "2_2") (pintype "passive"))
      (node (ref "T2") (pin "B") (pinfunction "B_B") (pintype "passive"))
    )
    (net (code "43") (name "Net-(U1-XTAL1)") (class "Default")
      (node (ref "C15") (pin "2") (pinfunction "2_2") (pintype "passive"))
      (node (ref "Q1") (pin "1") (pinfunction "1_1") (pintype "passive"))
      (node (ref "U1") (pin "8") (pinfunction "XTAL1_8") (pintype "bidirectional"))
    )
    (net (code "44") (name "Net-(U1-XTAL2)") (class "Default")
      (node (ref "C14") (pin "2") (pinfunction "2_2") (pintype "passive"))
      (node (ref "Q1") (pin "2") (pinfunction "2_2") (pintype "passive"))
      (node (ref "U1") (pin "7") (pinfunction "XTAL2_7") (pintype "bidirectional"))
    )
    (net (code "45") (name "RESET") (class "Default")
      (node (ref "PROG") (pin "1") (pinfunction "1_1") (pintype "passive"))
      (node (ref "R12") (pin "2") (pinfunction "2_2") (pintype "passive"))
      (node (ref "RESET") (pin "3") (pinfunction "2_3") (pintype "passive"))
      (node (ref "U1") (pin "4") (pinfunction "~{RESET}_4") (pintype "bidirectional"))
    )
    (net (code "46") (name "RX") (class "Default")
      (node (ref "SERIAL") (pin "2") (pinfunction "2_2") (pintype "passive"))
      (node (ref "U1") (pin "9") (pinfunction "PD0(PCINT24/RXD0)_9") (pintype "bidirectional"))
    )
    (net (code "47") (name "SCK") (class "Default")
      (node (ref "IC8") (pin "4") (pinfunction "SCK_4") (pintype "input"))
      (node (ref "PROG") (pin "2") (pinfunction "2_2") (pintype "passive"))
      (node (ref "U1") (pin "3") (pinfunction "PB7(PCINT15/SCK)_3") (pintype "bidirectional"))
    )
    (net (code "48") (name "SCL") (class "Default")
      (node (ref "PANEL") (pin "3") (pinfunction "3_3") (pintype "passive"))
      (node (ref "U1") (pin "19") (pinfunction "PC0(PCINT16/SCL)_19") (pintype "bidirectional"))
    )
    (net (code "49") (name "SDA") (class "Default")
      (node (ref "PANEL") (pin "2") (pinfunction "2_2") (pintype "passive"))
      (node (ref "U1") (pin "20") (pinfunction "PC1(PCINT17/SDA)_20") (pintype "bidirectional"))
    )
    (net (code "50") (name "TX") (class "Default")
      (node (ref "SERIAL") (pin "1") (pinfunction "1_1") (pintype "passive"))
      (node (ref "U1") (pin "10") (pinfunction "PD1(PCINT25/TXD0)_10") (pintype "bidirectional"))
    )
    (net (code "51") (name "VREF4096") (class "Default")
      (node (ref "C17") (pin "1") (pinfunction "1_1") (pintype "passive"))
      (node (ref "C20") (pin "+") (pinfunction "+_+") (pintype "passive"))
      (node (ref "IC7") (pin "2") (pinfunction "VOUT_2") (pintype "output"))
      (node (ref "IC8") (pin "11") (pinfunction "VREFB_11") (pintype "input"))
      (node (ref "IC8") (pin "13") (pinfunction "VREFA_13") (pintype "input"))
      (node (ref "U1") (pin "29") (pinfunction "AREF_29") (pintype "bidirectional"))
    )
    (net (code "52") (name "VSET") (class "Default")
      (node (ref "IC3") (pin "3") (pinfunction "+IN_3") (pintype "input"))
      (node (ref "IC8") (pin "14") (pinfunction "VOUTA_14") (pintype "output"))
    )
    (net (code "53") (name "unconnected-(H1-MOUNT-PadB3,0)") (class "Default")
      (node (ref "H1") (pin "B3,0") (pinfunction "MOUNT_B3,0") (pintype "passive"))
    )
    (net (code "54") (name "unconnected-(H2-MOUNT-PadB3,0)") (class "Default")
      (node (ref "H2") (pin "B3,0") (pinfunction "MOUNT_B3,0") (pintype "passive"))
    )
    (net (code "55") (name "unconnected-(H3-MOUNT-PadB3,0)") (class "Default")
      (node (ref "H3") (pin "B3,0") (pinfunction "MOUNT_B3,0") (pintype "passive"))
    )
    (net (code "56") (name "unconnected-(H4-MOUNT-PadB3,0)") (class "Default")
      (node (ref "H4") (pin "B3,0") (pinfunction "MOUNT_B3,0") (pintype "passive"))
    )
    (net (code "57") (name "unconnected-(U1-(ADC1{slash}PINT1)PA1-Pad36)") (class "Default")
      (node (ref "U1") (pin "36") (pinfunction "(ADC1/PINT1)PA1_36") (pintype "bidirectional"))
    )
    (net (code "58") (name "unconnected-(U1-(ADC2{slash}PINT2)PA2-Pad35)") (class "Default")
      (node (ref "U1") (pin "35") (pinfunction "(ADC2/PINT2)PA2_35") (pintype "bidirectional"))
    )
    (net (code "59") (name "unconnected-(U1-(ADC3{slash}PINT3)PA3-Pad34)") (class "Default")
      (node (ref "U1") (pin "34") (pinfunction "(ADC3/PINT3)PA3_34") (pintype "bidirectional"))
    )
    (net (code "60") (name "unconnected-(U1-(ADC7{slash}PINT7)PA7-Pad30)") (class "Default")
      (node (ref "U1") (pin "30") (pinfunction "(ADC7/PINT7)PA7_30") (pintype "bidirectional"))
    )
    (net (code "61") (name "unconnected-(U1-(TDI{slash}PCINT21)PC5-Pad24)") (class "Default")
      (node (ref "U1") (pin "24") (pinfunction "(TDI/PCINT21)PC5_24") (pintype "bidirectional"))
    )
    (net (code "62") (name "unconnected-(U1-(TDO{slash}PCINT20)PC4-Pad23)") (class "Default")
      (node (ref "U1") (pin "23") (pinfunction "(TDO/PCINT20)PC4_23") (pintype "bidirectional"))
    )
    (net (code "63") (name "unconnected-(U1-(TOSC1{slash}PCINT22)PC6-Pad25)") (class "Default")
      (node (ref "U1") (pin "25") (pinfunction "(TOSC1/PCINT22)PC6_25") (pintype "bidirectional"))
    )
    (net (code "64") (name "unconnected-(U1-(TOSC2{slash}PCINT22)PC7-Pad26)") (class "Default")
      (node (ref "U1") (pin "26") (pinfunction "(TOSC2/PCINT22)PC7_26") (pintype "bidirectional"))
    )
    (net (code "65") (name "unconnected-(U1-PC2(PCINT18{slash}TCK)-Pad21)") (class "Default")
      (node (ref "U1") (pin "21") (pinfunction "PC2(PCINT18/TCK)_21") (pintype "bidirectional"))
    )
    (net (code "66") (name "unconnected-(U1-PC3(PCINT19{slash}TMS)-Pad22)") (class "Default")
      (node (ref "U1") (pin "22") (pinfunction "PC3(PCINT19/TMS)_22") (pintype "bidirectional"))
    )
    (net (code "67") (name "unconnected-(U1-PD2(PCINT26{slash}INT0)-Pad11)") (class "Default")
      (node (ref "U1") (pin "11") (pinfunction "PD2(PCINT26/INT0)_11") (pintype "bidirectional"))
    )
    (net (code "68") (name "unconnected-(U1-PD3(PCINT27{slash}TXD1{slash}INT1)-Pad12)") (class "Default")
      (node (ref "U1") (pin "12") (pinfunction "PD3(PCINT27/TXD1/INT1)_12") (pintype "bidirectional"))
    )
  )
)
